# schematic.net
KiCad netlist of a schematic drawn in EAGLE
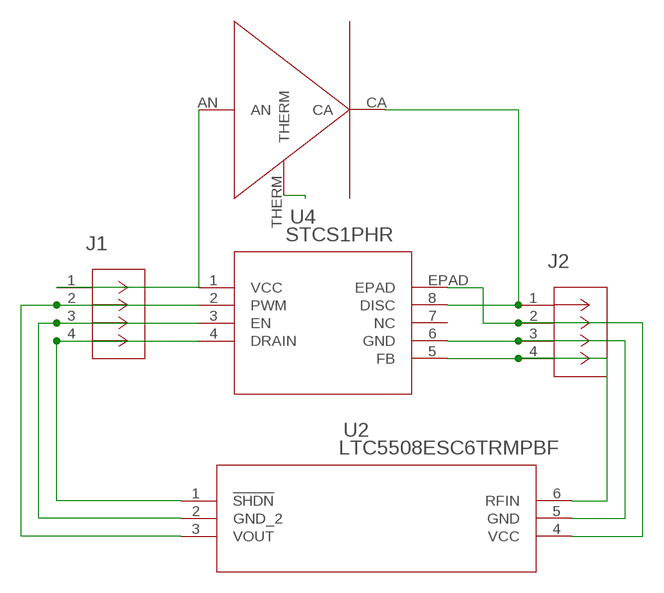
[diagram p0: schematic, sheet 1]

(export (version "E")
  (design (tool "Eeschema 10.0.6"))
  (components
    (comp (ref "J1")
      (value "61300411121")
      (footprint "eagle-import:CONN_61300411121_WRE")
      (fields (field (name "COPYRIGHT") "Copyright (C) 2022 Ultra Librarian. All rights reserved."))
      (libsource (lib "eagle-import") (part "61300411121"))
    )
    (comp (ref "J2")
      (value "61300411121")
      (footprint "eagle-import:CONN_61300411121_WRE")
      (fields (field (name "COPYRIGHT") "Copyright (C) 2022 Ultra Librarian. All rights reserved."))
      (libsource (lib "eagle-import") (part "61300411121"))
    )
    (comp (ref "U$1")
      (value "MKRAWT-02-0000-0D00J2051")
      (footprint "eagle-import:MKRAWT-02-0000-0D00J2051")
      (libsource (lib "eagle-import") (part "MKRAWT-02-0000-0D00J2051"))
    )
    (comp (ref "U2")
      (value "LTC5508ESC6TRMPBF")
      (footprint "eagle-import:SOT-6_SC_LIT")
      (fields
        (field (name "MANUFACTURER_PART_NUMBER") "LTC5508ESC6#TRMPBF")
        (field (name "COPYRIGHT") "Copyright (C) 2022 Ultra Librarian. All rights reserved.")
      )
      (libsource (lib "eagle-import") (part "LTC5508ESC6TRMPBF"))
    )
    (comp (ref "U4")
      (value "STCS1PHR")
      (footprint "eagle-import:POWERSO-8_STM")
      (fields (field (name "COPYRIGHT") "Copyright (C) 2022 Ultra Librarian. All rights reserved."))
      (libsource (lib "eagle-import") (part "STCS1PHR"))
    )
  )
  (nets
    (net (code "1") (name "Net-(U2-GND)") (class "Default")
      (node (ref "J2") (pin "3") (pinfunction "3_3") (pintype "passive"))
      (node (ref "U2") (pin "5") (pinfunction "GND_5") (pintype "power_in"))
      (node (ref "U4") (pin "6") (pinfunction "GND_6") (pintype "passive"))
    )
    (net (code "2") (name "Net-(U2-GND_2)") (class "Default")
      (node (ref "J1") (pin "3") (pinfunction "3_3") (pintype "passive"))
      (node (ref "U2") (pin "2") (pinfunction "GND_2_2") (pintype "power_in"))
      (node (ref "U4") (pin "3") (pinfunction "EN_3") (pintype "input"))
    )
    (net (code "3") (name "Net-(U2-RFIN)") (class "Default")
      (node (ref "J2") (pin "4") (pinfunction "4_4") (pintype "passive"))
      (node (ref "U2") (pin "6") (pinfunction "RFIN_6") (pintype "input"))
      (node (ref "U4") (pin "5") (pinfunction "FB_5") (pintype "input"))
    )
    (net (code "4") (name "Net-(U2-VCC)") (class "Default")
      (node (ref "J2") (pin "2") (pinfunction "2_2") (pintype "passive"))
      (node (ref "U2") (pin "4") (pinfunction "VCC_4") (pintype "power_in"))
      (node (ref "U4") (pin "EPAD") (pinfunction "EPAD_EPAD") (pintype "passive"))
    )
    (net (code "5") (name "Net-(U2-VOUT)") (class "Default")
      (node (ref "J1") (pin "2") (pinfunction "2_2") (pintype "passive"))
      (node (ref "U2") (pin "3") (pinfunction "VOUT_3") (pintype "output"))
      (node (ref "U4") (pin "2") (pinfunction "PWM_2") (pintype "input"))
    )
    (net (code "6") (name "Net-(U2-~{SHDN})") (class "Default")
      (node (ref "J1") (pin "4") (pinfunction "4_4") (pintype "passive"))
      (node (ref "U2") (pin "1") (pinfunction "~{SHDN}_1") (pintype "passive"))
      (node (ref "U4") (pin "4") (pinfunction "DRAIN_4") (pintype "output"))
    )
    (net (code "7") (name "Net-(U4-DISC)") (class "Default")
      (node (ref "J2") (pin "1") (pinfunction "1_1") (pintype "passive"))
      (node (ref "U$1") (pin "CA") (pinfunction "CA_CA") (pintype "passive"))
      (node (ref "U4") (pin "8") (pinfunction "DISC_8") (pintype "output"))
    )
    (net (code "8") (name "Net-(U4-VCC)") (class "Default")
      (node (ref "J1") (pin "1") (pinfunction "1_1") (pintype "passive"))
      (node (ref "U$1") (pin "AN") (pinfunction "AN_AN") (pintype "passive"))
      (node (ref "U4") (pin "1") (pinfunction "VCC_1") (pintype "power_in"))
    )
    (net (code "9") (name "unconnected-(U$1-PadTHERM)") (class "Default")
      (node (ref "U$1") (pin "THERM") (pinfunction "THERM_THERM") (pintype "passive"))
    )
    (net (code "10") (name "unconnected-(U4-NC-Pad7)") (class "Default")
      (node (ref "U4") (pin "7") (pinfunction "NC_7") (pintype "no_connect"))
    )
  )
)
